# Power_Regulation.net
KiCad netlist of a schematic drawn in Altium Designer
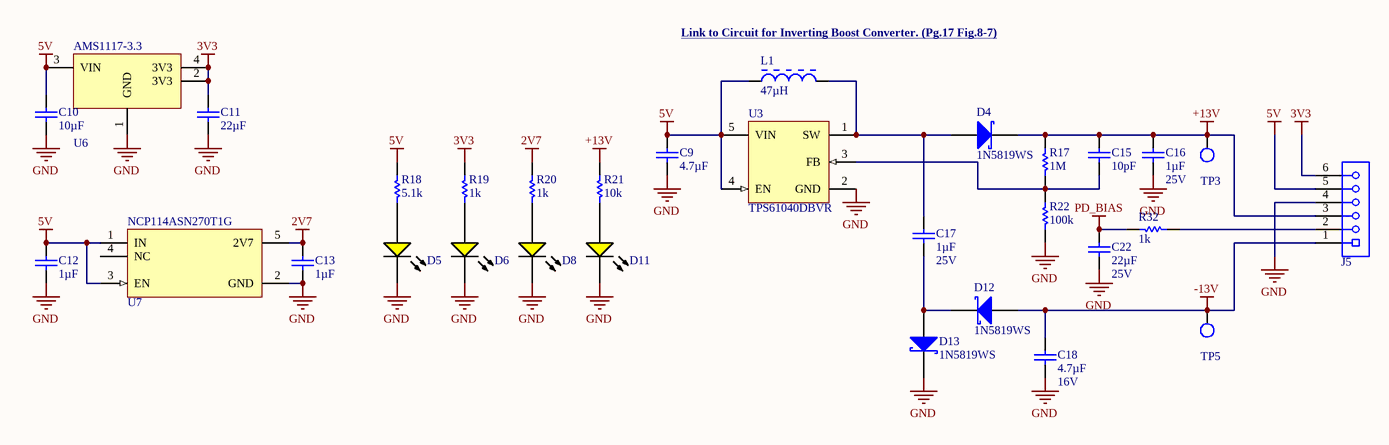
[diagram p0: Power_Regulation.SchDoc]

(export (version "E")
  (design (tool "Eeschema 10.0.6"))
  (components
    (comp (ref "C9")
      (value "4.7µF")
      (footprint "CAPC1608X10N")
      (description "16V 4.7uF X5R ±10% 0603 Multilayer Ceramic Capacitors MLCC - SMD/SMT ROHS")
      (fields (field (name "TOLERANCE") "10%") (field (name "Comment") "CL10A475KO8NNNC"))
      (libsource (lib "UWA Aerospace") (part "Capacitor - Non-polar"))
    )
    (comp (ref "C10")
      (value "10µF")
      (footprint "CAPC1005X06N")
      (description "Cap Ceramic 10uF 6.3V X5R 20% SMD 0402 85°C Paper T/R")
      (fields (field (name "TOLERANCE") "20%") (field (name "Comment") "CL05A106MQ5NUNC"))
      (libsource (lib "UWA Aerospace") (part "Capacitor - Non-polar"))
    )
    (comp (ref "C11")
      (value "22µF")
      (footprint "CAPC1608X10N")
      (description "Multilayer Ceramic Capacitor, 22 uF, 6.3 V, ± 20%, X5R, 0603 [1608 Metric]")
      (fields (field (name "TOLERANCE") "20%") (field (name "Comment") "CL10A226MQ8NRNC"))
      (libsource (lib "UWA Aerospace") (part "Capacitor - Non-polar"))
    )
    (comp (ref "C12")
      (value "1µF")
      (footprint "CAPC1005X06N")
      (fields (field (name "TOLERANCE") "10%") (field (name "Comment") "CL05A105KA5NQNC"))
      (libsource (lib "UWA Aerospace") (part "Capacitor - Non-polar"))
    )
    (comp (ref "C13")
      (value "1µF")
      (footprint "CAPC1005X06N")
      (fields (field (name "TOLERANCE") "10%") (field (name "Comment") "CL05A105KA5NQNC"))
      (libsource (lib "UWA Aerospace") (part "Capacitor - Non-polar"))
    )
    (comp (ref "C15")
      (value "10pF")
      (footprint "CAPC1005X06N")
      (description "Multilayer Ceramic Capacitor, 10 pF, 50 V, ± 5%, C0G (NP0), 0402 [1005 Metric]")
      (fields (field (name "TOLERANCE") "5%") (field (name "Comment") "CL05C100JB5NNNC"))
      (libsource (lib "UWA Aerospace") (part "Capacitor - Non-polar"))
    )
    (comp (ref "C16")
      (value "1µF")
      (footprint "CAPC1005X06N")
      (fields
        (field (name "VOLTAGE RATING") "25V")
        (field (name "TOLERANCE") "10%")
        (field (name "Comment") "CL05A105KA5NQNC")
      )
      (libsource (lib "UWA Aerospace") (part "Capacitor - Non-polar"))
    )
    (comp (ref "C17")
      (value "1µF")
      (footprint "CAPC1005X06N")
      (fields
        (field (name "VOLTAGE RATING") "25V")
        (field (name "TOLERANCE") "10%")
        (field (name "Comment") "CL05A105KA5NQNC")
      )
      (libsource (lib "UWA Aerospace") (part "Capacitor - Non-polar"))
    )
    (comp (ref "C18")
      (value "4.7µF")
      (footprint "CAPC1608X10N")
      (description "16V 4.7uF X5R ±10% 0603 Multilayer Ceramic Capacitors MLCC - SMD/SMT ROHS")
      (fields
        (field (name "VOLTAGE RATING") "16V")
        (field (name "TOLERANCE") "10%")
        (field (name "Comment") "CL10A475KO8NNNC")
      )
      (libsource (lib "UWA Aerospace") (part "Capacitor - Non-polar"))
    )
    (comp (ref "C22")
      (value "22µF")
      (footprint "CAPC2012X14N")
      (fields
        (field (name "VOLTAGE RATING") "25V")
        (field (name "TOLERANCE") "20%")
        (field (name "Comment") "CL21A226MAQNNNE")
      )
      (libsource (lib "UWA Aerospace") (part "Capacitor - Non-polar"))
    )
    (comp (ref "D4")
      (value "1N5819WS")
      (footprint "SODFL250X100-2N")
      (description "VR=40V IF=1A 120pF P=250mW")
      (libsource (lib "UWA Aerospace") (part "Diode - Schottky"))
    )
    (comp (ref "D5")
      (value "KT-0805Y")
      (footprint "LED_0805")
      (description "Yellow 0805 LED Indication - Discrete ROHS")
      (libsource (lib "UWA Aerospace") (part "LED - Yellow"))
    )
    (comp (ref "D6")
      (value "KT-0805Y")
      (footprint "LED_0805")
      (description "Yellow 0805 LED Indication - Discrete ROHS")
      (libsource (lib "UWA Aerospace") (part "LED - Yellow"))
    )
    (comp (ref "D8")
      (value "KT-0805Y")
      (footprint "LED_0805")
      (description "Yellow 0805 LED Indication - Discrete ROHS")
      (libsource (lib "UWA Aerospace") (part "LED - Yellow"))
    )
    (comp (ref "D11")
      (value "KT-0805Y")
      (footprint "LED_0805")
      (description "Yellow 0805 LED Indication - Discrete ROHS")
      (libsource (lib "UWA Aerospace") (part "LED - Yellow"))
    )
    (comp (ref "D12")
      (value "1N5819WS")
      (footprint "SODFL250X100-2N")
      (description "VR=40V IF=1A 120pF P=250mW")
      (libsource (lib "UWA Aerospace") (part "Diode - Schottky"))
    )
    (comp (ref "D13")
      (value "1N5819WS")
      (footprint "SODFL250X100-2N")
      (description "VR=40V IF=1A 120pF P=250mW")
      (libsource (lib "UWA Aerospace") (part "Diode - Schottky"))
    )
    (comp (ref "J5")
      (value "68000-406HLF")
      (footprint "68000-406HLF-Footprint-1")
      (description "CONN HEADER 6POS .100 STR TIN")
      (fields (field (name "SOURCE") "Aliexpress"))
      (libsource (lib "UWA Aerospace") (part "68000-406HLF"))
    )
    (comp (ref "L1")
      (value "47µH")
      (footprint "INDP5252X48L")
      (description "General Purpose Inductor, 47uH, 20%, 1 Element, SMD, 2320")
      (fields
        (field (name "TOLERANCE") "20%")
        (field (name "Comment") "PCD0504MT470")
        (field (name "SOURCE") "UWAA_Stock")
      )
      (libsource (lib "UWA Aerospace") (part "Inductor - Ferrite Core"))
    )
    (comp (ref "R17")
      (value "1M")
      (footprint "RESC1005X04N")
      (fields (field (name "TOLERANCE") "1%") (field (name "Comment") "0402WGF1004TCE"))
      (libsource (lib "UWA Aerospace") (part "Resistor"))
    )
    (comp (ref "R18")
      (value "5.1k")
      (footprint "RESC1005X04N")
      (fields (field (name "TOLERANCE") "1%") (field (name "Comment") "0402WGF5101TCE"))
      (libsource (lib "UWA Aerospace") (part "Resistor"))
    )
    (comp (ref "R19")
      (value "1k")
      (footprint "RESC1005X04N")
      (description "RES 1K OHM 1% 1/16W 0402")
      (fields (field (name "TOLERANCE") "1%") (field (name "Comment") "CRCW04021K00FKEDC"))
      (libsource (lib "UWA Aerospace") (part "WSLP1206R0500FEA"))
    )
    (comp (ref "R20")
      (value "1k")
      (footprint "RESC1005X04N")
      (description "RES 1K OHM 1% 1/16W 0402")
      (fields (field (name "TOLERANCE") "1%") (field (name "Comment") "CRCW04021K00FKEDC"))
      (libsource (lib "UWA Aerospace") (part "WSLP1206R0500FEA"))
    )
    (comp (ref "R21")
      (value "10k")
      (footprint "RESC1005X04N")
      (description "Res Thick Film 0402 10K Ohm 1% 1/16W ±100ppm/°C Molded SMD Paper T/R")
      (fields (field (name "TOLERANCE") "1%") (field (name "Comment") "CRCW0402-10K0FKED"))
      (libsource (lib "UWA Aerospace") (part "Resistor"))
    )
    (comp (ref "R22")
      (value "100k")
      (footprint "RESC1005X04N")
      (description "RES 100K OHM 1% 1/16W 0402")
      (fields (field (name "TOLERANCE") "1%") (field (name "Comment") "CRCW0402100KFKEDC"))
      (libsource (lib "UWA Aerospace") (part "WSLP1206R0500FEA"))
    )
    (comp (ref "R32")
      (value "1k")
      (footprint "RESC1005X04N")
      (description "RES 1K OHM 1% 1/16W 0402")
      (fields (field (name "TOLERANCE") "1%") (field (name "Comment") "CRCW04021K00FKEDC"))
      (libsource (lib "UWA Aerospace") (part "WSLP1206R0500FEA"))
    )
    (comp (ref "TP3")
      (value "Test Point 5001")
      (footprint "FP-5001-MFG")
      (fields (field (name "SOURCE") "UWAA_Stock"))
      (libsource (lib "UWA Aerospace") (part "Test Point"))
    )
    (comp (ref "TP5")
      (value "Test Point 5001")
      (footprint "FP-5001-MFG")
      (fields (field (name "SOURCE") "UWAA_Stock"))
      (libsource (lib "UWA Aerospace") (part "Test Point"))
    )
    (comp (ref "U3")
      (value "TPS61040DBVR")
      (footprint "DBV0005A_L")
      (description "Conv DC-DC 1.8V to 6V Step Up Single-Out 1.8V to 28V 0.4A 5-Pin SOT-23 T/R")
      (libsource (lib "UWA Aerospace") (part "TI-TPS61040DBV5"))
    )
    (comp (ref "U6")
      (value "AMS1117-3.3")
      (footprint "1117_REG_SOT223__SOT230P700X180-4L")
      (libsource (lib "UWA Aerospace") (part "8bdbb5f8e77002000e30dd2845d0354"))
    )
    (comp (ref "U7")
      (value "NCP114ASN270T1G")
      (footprint "SOT95P280X110-5N")
      (description "LDO Voltage Regulator, Fixed, 1.7V to 5.5V, Single Output, 170mV, 2.7V, 300mA, 5 Pins, TSOP")
      (fields (field (name "SOURCE") "Distributor"))
      (libsource (lib "UWA Aerospace") (part "NCP114ASN270T1G-Symbol-1"))
    )
  )
  (nets
    (net (code "1") (name "+13V") (class "Default")
      (node (ref "C15") (pin "2") (pinfunction "2_2") (pintype "passive"))
      (node (ref "C16") (pin "2") (pinfunction "2_2") (pintype "passive"))
      (node (ref "D4") (pin "1") (pinfunction "K_1") (pintype "passive"))
      (node (ref "J5") (pin "3") (pinfunction "3_3") (pintype "passive"))
      (node (ref "R17") (pin "1") (pinfunction "1_1") (pintype "passive"))
      (node (ref "R21") (pin "2") (pinfunction "2_2") (pintype "passive"))
      (node (ref "TP3") (pin "1") (pinfunction "1_1") (pintype "passive"))
    )
    (net (code "2") (name "-13V") (class "Default")
      (node (ref "C18") (pin "2") (pinfunction "2_2") (pintype "passive"))
      (node (ref "D12") (pin "2") (pinfunction "A_2") (pintype "passive"))
      (node (ref "J5") (pin "1") (pinfunction "1_1") (pintype "passive"))
      (node (ref "TP5") (pin "1") (pinfunction "1_1") (pintype "passive"))
    )
    (net (code "3") (name "2V7") (class "Default")
      (node (ref "C13") (pin "2") (pinfunction "2_2") (pintype "passive"))
      (node (ref "R20") (pin "2") (pinfunction "2_2") (pintype "passive"))
      (node (ref "U7") (pin "5") (pinfunction "2V7_5") (pintype "power_in"))
    )
    (net (code "4") (name "3V3") (class "Default")
      (node (ref "C11") (pin "2") (pinfunction "2_2") (pintype "passive"))
      (node (ref "J5") (pin "6") (pinfunction "6_6") (pintype "passive"))
      (node (ref "R19") (pin "2") (pinfunction "2_2") (pintype "passive"))
      (node (ref "U6") (pin "2") (pinfunction "3V3_2") (pintype "passive"))
      (node (ref "U6") (pin "4") (pinfunction "3V3_4") (pintype "passive"))
    )
    (net (code "5") (name "5V") (class "Default")
      (node (ref "C10") (pin "2") (pinfunction "2_2") (pintype "passive"))
      (node (ref "C12") (pin "2") (pinfunction "2_2") (pintype "passive"))
      (node (ref "C9") (pin "2") (pinfunction "2_2") (pintype "passive"))
      (node (ref "J5") (pin "5") (pinfunction "5_5") (pintype "passive"))
      (node (ref "L1") (pin "1") (pinfunction "1_1") (pintype "passive"))
      (node (ref "R18") (pin "2") (pinfunction "2_2") (pintype "passive"))
      (node (ref "U3") (pin "4") (pinfunction "EN_4") (pintype "input"))
      (node (ref "U3") (pin "5") (pinfunction "VIN_5") (pintype "power_in"))
      (node (ref "U6") (pin "3") (pinfunction "VIN_3") (pintype "power_in"))
      (node (ref "U7") (pin "1") (pinfunction "IN_1") (pintype "power_in"))
      (node (ref "U7") (pin "3") (pinfunction "EN_3") (pintype "input"))
    )
    (net (code "6") (name "GND") (class "Default")
      (node (ref "C10") (pin "1") (pinfunction "1_1") (pintype "passive"))
      (node (ref "C11") (pin "1") (pinfunction "1_1") (pintype "passive"))
      (node (ref "C12") (pin "1") (pinfunction "1_1") (pintype "passive"))
      (node (ref "C13") (pin "1") (pinfunction "1_1") (pintype "passive"))
      (node (ref "C16") (pin "1") (pinfunction "1_1") (pintype "passive"))
      (node (ref "C18") (pin "1") (pinfunction "1_1") (pintype "passive"))
      (node (ref "C22") (pin "1") (pinfunction "1_1") (pintype "passive"))
      (node (ref "C9") (pin "1") (pinfunction "1_1") (pintype "passive"))
      (node (ref "D11") (pin "1") (pinfunction "K_1") (pintype "passive"))
      (node (ref "D13") (pin "1") (pinfunction "K_1") (pintype "passive"))
      (node (ref "D5") (pin "1") (pinfunction "K_1") (pintype "passive"))
      (node (ref "D6") (pin "1") (pinfunction "K_1") (pintype "passive"))
      (node (ref "D8") (pin "1") (pinfunction "K_1") (pintype "passive"))
      (node (ref "J5") (pin "4") (pinfunction "4_4") (pintype "passive"))
      (node (ref "R22") (pin "2") (pinfunction "2_2") (pintype "passive"))
      (node (ref "U3") (pin "2") (pinfunction "GND_2") (pintype "power_in"))
      (node (ref "U6") (pin "1") (pinfunction "GND_1") (pintype "power_in"))
      (node (ref "U7") (pin "2") (pinfunction "GND_2") (pintype "power_in"))
    )
    (net (code "7") (name "Net-(D4-A)") (class "Default")
      (node (ref "C17") (pin "2") (pinfunction "2_2") (pintype "passive"))
      (node (ref "D4") (pin "2") (pinfunction "A_2") (pintype "passive"))
      (node (ref "L1") (pin "2") (pinfunction "2_2") (pintype "passive"))
      (node (ref "U3") (pin "1") (pinfunction "SW_1") (pintype "power_in"))
    )
    (net (code "8") (name "Net-(D5-A)") (class "Default")
      (node (ref "D5") (pin "2") (pinfunction "A_2") (pintype "passive"))
      (node (ref "R18") (pin "1") (pinfunction "1_1") (pintype "passive"))
    )
    (net (code "9") (name "Net-(D6-A)") (class "Default")
      (node (ref "D6") (pin "2") (pinfunction "A_2") (pintype "passive"))
      (node (ref "R19") (pin "1") (pinfunction "1_1") (pintype "passive"))
    )
    (net (code "10") (name "Net-(D8-A)") (class "Default")
      (node (ref "D8") (pin "2") (pinfunction "A_2") (pintype "passive"))
      (node (ref "R20") (pin "1") (pinfunction "1_1") (pintype "passive"))
    )
    (net (code "11") (name "Net-(D11-A)") (class "Default")
      (node (ref "D11") (pin "2") (pinfunction "A_2") (pintype "passive"))
      (node (ref "R21") (pin "1") (pinfunction "1_1") (pintype "passive"))
    )
    (net (code "12") (name "Net-(D12-K)") (class "Default")
      (node (ref "C17") (pin "1") (pinfunction "1_1") (pintype "passive"))
      (node (ref "D12") (pin "1") (pinfunction "K_1") (pintype "passive"))
      (node (ref "D13") (pin "2") (pinfunction "A_2") (pintype "passive"))
    )
    (net (code "13") (name "Net-(J5-Pad2)") (class "Default")
      (node (ref "J5") (pin "2") (pinfunction "2_2") (pintype "passive"))
      (node (ref "R32") (pin "2") (pinfunction "2_2") (pintype "passive"))
    )
    (net (code "14") (name "Net-(U3-FB)") (class "Default")
      (node (ref "C15") (pin "1") (pinfunction "1_1") (pintype "passive"))
      (node (ref "R17") (pin "2") (pinfunction "2_2") (pintype "passive"))
      (node (ref "R22") (pin "1") (pinfunction "1_1") (pintype "passive"))
      (node (ref "U3") (pin "3") (pinfunction "FB_3") (pintype "input"))
    )
    (net (code "15") (name "PD_BIAS") (class "Default")
      (node (ref "C22") (pin "2") (pinfunction "2_2") (pintype "passive"))
      (node (ref "R32") (pin "1") (pinfunction "1_1") (pintype "passive"))
    )
    (net (code "16") (name "unconnected-(U7-NC-Pad4)") (class "Default")
      (node (ref "U7") (pin "4") (pinfunction "NC_4") (pintype "passive"))
    )
  )
)
